# Power.net
KiCad netlist of a schematic drawn in Altium Designer
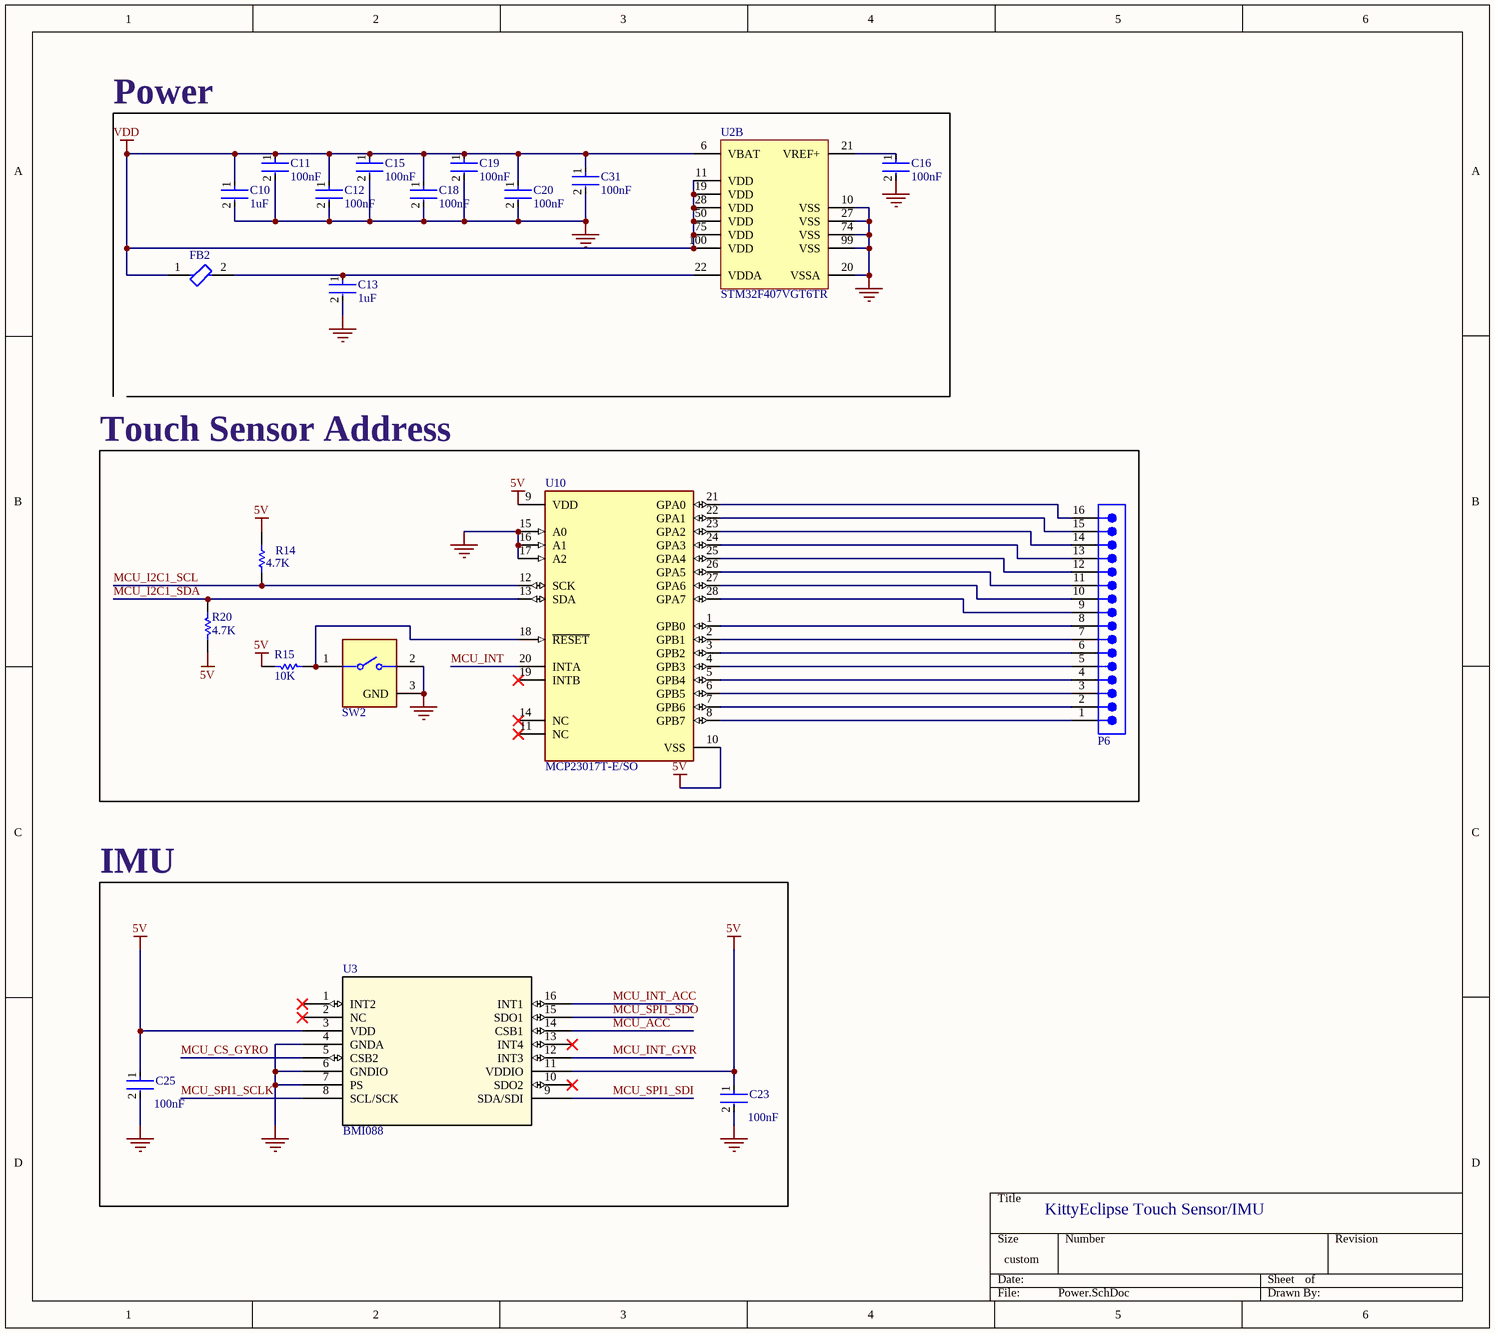
[diagram p0: Power.SchDoc]

(export (version "E")
  (design (tool "Eeschema 10.0.6"))
  (components
    (comp (ref "C10")
      (value "1uF")
      (footprint "FP-CL10-IPC_C")
      (description "Cap Ceramic 1uF 10V X7R ±10% Pad SMD 0603 +125°C T/R")
      (fields (field (name "TOLERANCE") "10%"))
      (libsource (lib "Altium Content Vault") (part "b4654b650e69147ec39a6b967a45e02"))
    )
    (comp (ref "C11")
      (value "100nF")
      (footprint "FP-CL93-IPC_C")
      (description "Cap Ceramic 100nF 10V X7R ±10% SMD 0402 +125°C Paper T/R")
      (libsource (lib "Altium Content Vault") (part "b4654b650e69147ec39a6b967a45e02"))
    )
    (comp (ref "C12")
      (value "100nF")
      (footprint "FP-CL93-IPC_C")
      (description "Cap Ceramic 100nF 10V X7R ±10% SMD 0402 +125°C Paper T/R")
      (libsource (lib "Altium Content Vault") (part "b4654b650e69147ec39a6b967a45e02"))
    )
    (comp (ref "C13")
      (value "1uF")
      (footprint "FP-CL10-IPC_C")
      (description "Cap Ceramic 1uF 10V X7R ±10% Pad SMD 0603 +125°C T/R")
      (fields (field (name "TOLERANCE") "10%"))
      (libsource (lib "Altium Content Vault") (part "b4654b650e69147ec39a6b967a45e02"))
    )
    (comp (ref "C15")
      (value "100nF")
      (footprint "FP-CL93-IPC_C")
      (description "Cap Ceramic 100nF 10V X7R ±10% SMD 0402 +125°C Paper T/R")
      (libsource (lib "Altium Content Vault") (part "b4654b650e69147ec39a6b967a45e02"))
    )
    (comp (ref "C16")
      (value "100nF")
      (footprint "FP-CL93-IPC_C")
      (description "Cap Ceramic 100nF 10V X7R ±10% SMD 0402 +125°C Paper T/R")
      (libsource (lib "Altium Content Vault") (part "b4654b650e69147ec39a6b967a45e02"))
    )
    (comp (ref "C18")
      (value "100nF")
      (footprint "FP-CL93-IPC_C")
      (description "Cap Ceramic 100nF 10V X7R ±10% SMD 0402 +125°C Paper T/R")
      (libsource (lib "Altium Content Vault") (part "b4654b650e69147ec39a6b967a45e02"))
    )
    (comp (ref "C19")
      (value "100nF")
      (footprint "FP-CL93-IPC_C")
      (description "Cap Ceramic 100nF 10V X7R ±10% SMD 0402 +125°C Paper T/R")
      (libsource (lib "Altium Content Vault") (part "b4654b650e69147ec39a6b967a45e02"))
    )
    (comp (ref "C20")
      (value "100nF")
      (footprint "FP-CL93-IPC_C")
      (description "Cap Ceramic 100nF 10V X7R ±10% SMD 0402 +125°C Paper T/R")
      (libsource (lib "Altium Content Vault") (part "b4654b650e69147ec39a6b967a45e02"))
    )
    (comp (ref "C23")
      (value "100nF")
      (footprint "FP-CL93-IPC_C")
      (description "Cap Ceramic 100nF 10V X7R ±10% SMD 0402 +125°C Paper T/R")
      (libsource (lib "Altium Content Vault") (part "b4654b650e69147ec39a6b967a45e02"))
    )
    (comp (ref "C25")
      (value "100nF")
      (footprint "FP-CL93-IPC_C")
      (description "Cap Ceramic 100nF 10V X7R ±10% SMD 0402 +125°C Paper T/R")
      (libsource (lib "Altium Content Vault") (part "b4654b650e69147ec39a6b967a45e02"))
    )
    (comp (ref "C31")
      (value "100nF")
      (footprint "FP-CL93-IPC_C")
      (description "Cap Ceramic 100nF 10V X7R ±10% SMD 0402 +125°C Paper T/R")
      (libsource (lib "Altium Content Vault") (part "b4654b650e69147ec39a6b967a45e02"))
    )
    (comp (ref "FB2")
      (value "600ohm")
      (footprint "FP-BLM15-0_05-MFG")
      (description "Chip Ferrite Bead, 0402, 600Ω @ 100MHz, 0.52Ω, 25%, 300mA")
      (fields (field (name "TOLERANCE") "25%"))
      (libsource (lib "Altium Content Vault") (part "5f30dd21d616792df468990f7003faa"))
    )
    (comp (ref "P6")
      (value "61301611121")
      (footprint "61301611121")
      (libsource (lib "Altium Content Vault") (part "Header_Male_1R_16P"))
    )
    (comp (ref "R14")
      (value "4.7K")
      (footprint "RESC1608X55X25LL10T15")
      (description "Chip Resistor, 4.7 KOhm, +/- 1%, 0.1 W, -55 to 155 degC, 0603 (1608 Metric), RoHS, Tape and Reel")
      (fields (field (name "MANUFACTURER") "Yageo") (field (name "TOLERANCE") "1%"))
      (libsource (lib "Altium Content Vault") (part "RES-2"))
    )
    (comp (ref "R15")
      (value "10K")
      (footprint "RESC1608X55X25ML10T15")
      (description "Resistor, 10 KOhm, +/- 5%, 100 mW, -55 to 155 degC, 0603 (1608 Metric), RoHS, Tape and Reel")
      (fields (field (name "MANUFACTURER") "Yageo") (field (name "TOLERANCE") "5%"))
      (libsource (lib "Altium Content Vault") (part "RES-2"))
    )
    (comp (ref "R20")
      (value "4.7K")
      (footprint "RESC1608X55X25LL10T15")
      (description "Chip Resistor, 4.7 KOhm, +/- 1%, 0.1 W, -55 to 155 degC, 0603 (1608 Metric), RoHS, Tape and Reel")
      (fields (field (name "MANUFACTURER") "Yageo") (field (name "TOLERANCE") "1%"))
      (libsource (lib "Altium Content Vault") (part "RES-2"))
    )
    (comp (ref "SW2")
      (value "B3U-1100PM")
      (footprint "FP-B3U-1100PM-MFG")
      (description "SWITCH TACTILE SPST-NO 0.05A 12V")
      (libsource (lib "Altium Content Vault") (part "6d7322ea62e06c21cb959ab9578dfa0"))
    )
    (comp (ref "U2")
      (value "STM32F407VGT6TR")
      (footprint "STM-LQFP100_L")
      (fields (field (name "MANUFACTURER") "STMicroelectronics"))
      (libsource (lib "Altium Content Vault") (part "MC-ARM-STM32F40X_41X-SQ100"))
    )
    (comp (ref "U3")
      (value "BMI088")
      (footprint "QFN_BMI085_BOS")
      (description "No Description Available")
      (libsource (lib "BMI088") (part "BMI088"))
    )
    (comp (ref "U10")
      (value "MCP23017T-E/SO")
      (footprint "FP-C04-052-MFG")
      (description "IC I/O EXPANDER I2C 16B 28SOIC")
      (libsource (lib "Altium Content Vault") (part "5a9070f3ac31e52c3c9f34e69183557"))
    )
  )
  (nets
    (net (code "1") (name "/MCU_ACC") (class "Default")
      (node (ref "U3") (pin "14") (pinfunction "CSB1_14") (pintype "bidirectional"))
    )
    (net (code "2") (name "/MCU_CS_GYRO") (class "Default")
      (node (ref "U3") (pin "5") (pinfunction "CSB2_5") (pintype "bidirectional"))
    )
    (net (code "3") (name "/MCU_I2C1_SCL") (class "Default")
      (node (ref "R14") (pin "2") (pinfunction "2_2") (pintype "passive"))
      (node (ref "U10") (pin "12") (pinfunction "SCK_12") (pintype "bidirectional"))
    )
    (net (code "4") (name "/MCU_I2C1_SDA") (class "Default")
      (node (ref "R20") (pin "2") (pinfunction "2_2") (pintype "passive"))
      (node (ref "U10") (pin "13") (pinfunction "SDA_13") (pintype "bidirectional"))
    )
    (net (code "5") (name "/MCU_INT") (class "Default")
      (node (ref "U10") (pin "20") (pinfunction "INTA_20") (pintype "open_collector"))
    )
    (net (code "6") (name "/MCU_INT_ACC") (class "Default")
      (node (ref "U3") (pin "16") (pinfunction "INT1_16") (pintype "bidirectional"))
    )
    (net (code "7") (name "/MCU_INT_GYR") (class "Default")
      (node (ref "U3") (pin "12") (pinfunction "INT3_12") (pintype "bidirectional"))
    )
    (net (code "8") (name "/MCU_SPI1_SCLK") (class "Default")
      (node (ref "U3") (pin "8") (pinfunction "SCL/SCK_8") (pintype "passive"))
    )
    (net (code "9") (name "/MCU_SPI1_SDI") (class "Default")
      (node (ref "U3") (pin "9") (pinfunction "SDA/SDI_9") (pintype "passive"))
    )
    (net (code "10") (name "/MCU_SPI1_SDO") (class "Default")
      (node (ref "U3") (pin "15") (pinfunction "SDO1_15") (pintype "bidirectional"))
    )
    (net (code "11") (name "5V") (class "Default")
      (node (ref "C23") (pin "1") (pinfunction "1_1") (pintype "passive"))
      (node (ref "C25") (pin "1") (pinfunction "1_1") (pintype "passive"))
      (node (ref "R14") (pin "1") (pinfunction "1_1") (pintype "passive"))
      (node (ref "R15") (pin "1") (pinfunction "1_1") (pintype "passive"))
      (node (ref "R20") (pin "1") (pinfunction "1_1") (pintype "passive"))
      (node (ref "U10") (pin "10") (pinfunction "VSS_10") (pintype "power_in"))
      (node (ref "U10") (pin "9") (pinfunction "VDD_9") (pintype "power_in"))
      (node (ref "U3") (pin "11") (pinfunction "VDDIO_11") (pintype "power_in"))
      (node (ref "U3") (pin "3") (pinfunction "VDD_3") (pintype "power_in"))
    )
    (net (code "12") (name "GND") (class "Default")
      (node (ref "C10") (pin "2") (pinfunction "2_2") (pintype "passive"))
      (node (ref "C11") (pin "2") (pinfunction "2_2") (pintype "passive"))
      (node (ref "C12") (pin "2") (pinfunction "2_2") (pintype "passive"))
      (node (ref "C13") (pin "2") (pinfunction "2_2") (pintype "passive"))
      (node (ref "C15") (pin "2") (pinfunction "2_2") (pintype "passive"))
      (node (ref "C16") (pin "2") (pinfunction "2_2") (pintype "passive"))
      (node (ref "C18") (pin "2") (pinfunction "2_2") (pintype "passive"))
      (node (ref "C19") (pin "2") (pinfunction "2_2") (pintype "passive"))
      (node (ref "C20") (pin "2") (pinfunction "2_2") (pintype "passive"))
      (node (ref "C23") (pin "2") (pinfunction "2_2") (pintype "passive"))
      (node (ref "C25") (pin "2") (pinfunction "2_2") (pintype "passive"))
      (node (ref "C31") (pin "2") (pinfunction "2_2") (pintype "passive"))
      (node (ref "SW2") (pin "2") (pinfunction "2_2") (pintype "passive"))
      (node (ref "SW2") (pin "3") (pinfunction "GND_3") (pintype "power_in"))
      (node (ref "U10") (pin "15") (pinfunction "A0_15") (pintype "input"))
      (node (ref "U10") (pin "16") (pinfunction "A1_16") (pintype "input"))
      (node (ref "U10") (pin "17") (pinfunction "A2_17") (pintype "input"))
      (node (ref "U2") (pin "10") (pinfunction "VSS_10") (pintype "power_in"))
      (node (ref "U2") (pin "20") (pinfunction "VSSA_20") (pintype "power_in"))
      (node (ref "U2") (pin "27") (pinfunction "VSS_27") (pintype "power_in"))
      (node (ref "U2") (pin "74") (pinfunction "VSS_74") (pintype "power_in"))
      (node (ref "U2") (pin "99") (pinfunction "VSS_99") (pintype "power_in"))
      (node (ref "U3") (pin "4") (pinfunction "GNDA_4") (pintype "power_in"))
      (node (ref "U3") (pin "6") (pinfunction "GNDIO_6") (pintype "power_in"))
      (node (ref "U3") (pin "7") (pinfunction "PS_7") (pintype "passive"))
    )
    (net (code "13") (name "Net-(U2B-VDDA)") (class "Default")
      (node (ref "C13") (pin "1") (pinfunction "1_1") (pintype "passive"))
      (node (ref "FB2") (pin "2") (pinfunction "2_2") (pintype "passive"))
      (node (ref "U2") (pin "22") (pinfunction "VDDA_22") (pintype "power_in"))
    )
    (net (code "14") (name "Net-(U2B-VREF+)") (class "Default")
      (node (ref "C16") (pin "1") (pinfunction "1_1") (pintype "passive"))
      (node (ref "U2") (pin "21") (pinfunction "VREF+_21") (pintype "power_in"))
    )
    (net (code "15") (name "Net-(U10-GPA0)") (class "Default")
      (node (ref "P6") (pin "16") (pinfunction "16_16") (pintype "passive"))
      (node (ref "U10") (pin "21") (pinfunction "GPA0_21") (pintype "bidirectional"))
    )
    (net (code "16") (name "Net-(U10-GPA1)") (class "Default")
      (node (ref "P6") (pin "15") (pinfunction "15_15") (pintype "passive"))
      (node (ref "U10") (pin "22") (pinfunction "GPA1_22") (pintype "bidirectional"))
    )
    (net (code "17") (name "Net-(U10-GPA2)") (class "Default")
      (node (ref "P6") (pin "14") (pinfunction "14_14") (pintype "passive"))
      (node (ref "U10") (pin "23") (pinfunction "GPA2_23") (pintype "bidirectional"))
    )
    (net (code "18") (name "Net-(U10-GPA3)") (class "Default")
      (node (ref "P6") (pin "13") (pinfunction "13_13") (pintype "passive"))
      (node (ref "U10") (pin "24") (pinfunction "GPA3_24") (pintype "bidirectional"))
    )
    (net (code "19") (name "Net-(U10-GPA4)") (class "Default")
      (node (ref "P6") (pin "12") (pinfunction "12_12") (pintype "passive"))
      (node (ref "U10") (pin "25") (pinfunction "GPA4_25") (pintype "bidirectional"))
    )
    (net (code "20") (name "Net-(U10-GPA5)") (class "Default")
      (node (ref "P6") (pin "11") (pinfunction "11_11") (pintype "passive"))
      (node (ref "U10") (pin "26") (pinfunction "GPA5_26") (pintype "bidirectional"))
    )
    (net (code "21") (name "Net-(U10-GPA6)") (class "Default")
      (node (ref "P6") (pin "10") (pinfunction "10_10") (pintype "passive"))
      (node (ref "U10") (pin "27") (pinfunction "GPA6_27") (pintype "bidirectional"))
    )
    (net (code "22") (name "Net-(U10-GPA7)") (class "Default")
      (node (ref "P6") (pin "9") (pinfunction "9_9") (pintype "passive"))
      (node (ref "U10") (pin "28") (pinfunction "GPA7_28") (pintype "bidirectional"))
    )
    (net (code "23") (name "Net-(U10-GPB0)") (class "Default")
      (node (ref "P6") (pin "8") (pinfunction "8_8") (pintype "passive"))
      (node (ref "U10") (pin "1") (pinfunction "GPB0_1") (pintype "bidirectional"))
    )
    (net (code "24") (name "Net-(U10-GPB1)") (class "Default")
      (node (ref "P6") (pin "7") (pinfunction "7_7") (pintype "passive"))
      (node (ref "U10") (pin "2") (pinfunction "GPB1_2") (pintype "bidirectional"))
    )
    (net (code "25") (name "Net-(U10-GPB2)") (class "Default")
      (node (ref "P6") (pin "6") (pinfunction "6_6") (pintype "passive"))
      (node (ref "U10") (pin "3") (pinfunction "GPB2_3") (pintype "bidirectional"))
    )
    (net (code "26") (name "Net-(U10-GPB3)") (class "Default")
      (node (ref "P6") (pin "5") (pinfunction "5_5") (pintype "passive"))
      (node (ref "U10") (pin "4") (pinfunction "GPB3_4") (pintype "bidirectional"))
    )
    (net (code "27") (name "Net-(U10-GPB4)") (class "Default")
      (node (ref "P6") (pin "4") (pinfunction "4_4") (pintype "passive"))
      (node (ref "U10") (pin "5") (pinfunction "GPB4_5") (pintype "bidirectional"))
    )
    (net (code "28") (name "Net-(U10-GPB5)") (class "Default")
      (node (ref "P6") (pin "3") (pinfunction "3_3") (pintype "passive"))
      (node (ref "U10") (pin "6") (pinfunction "GPB5_6") (pintype "bidirectional"))
    )
    (net (code "29") (name "Net-(U10-GPB6)") (class "Default")
      (node (ref "P6") (pin "2") (pinfunction "2_2") (pintype "passive"))
      (node (ref "U10") (pin "7") (pinfunction "GPB6_7") (pintype "bidirectional"))
    )
    (net (code "30") (name "Net-(U10-GPB7)") (class "Default")
      (node (ref "P6") (pin "1") (pinfunction "1_1") (pintype "passive"))
      (node (ref "U10") (pin "8") (pinfunction "GPB7_8") (pintype "bidirectional"))
    )
    (net (code "31") (name "Net-(U10-~{RESET})") (class "Default")
      (node (ref "R15") (pin "2") (pinfunction "2_2") (pintype "passive"))
      (node (ref "SW2") (pin "1") (pinfunction "1_1") (pintype "passive"))
      (node (ref "U10") (pin "18") (pinfunction "~{RESET}_18") (pintype "input"))
    )
    (net (code "32") (name "VDD") (class "Default")
      (node (ref "C10") (pin "1") (pinfunction "1_1") (pintype "passive"))
      (node (ref "C11") (pin "1") (pinfunction "1_1") (pintype "passive"))
      (node (ref "C12") (pin "1") (pinfunction "1_1") (pintype "passive"))
      (node (ref "C15") (pin "1") (pinfunction "1_1") (pintype "passive"))
      (node (ref "C18") (pin "1") (pinfunction "1_1") (pintype "passive"))
      (node (ref "C19") (pin "1") (pinfunction "1_1") (pintype "passive"))
      (node (ref "C20") (pin "1") (pinfunction "1_1") (pintype "passive"))
      (node (ref "C31") (pin "1") (pinfunction "1_1") (pintype "passive"))
      (node (ref "FB2") (pin "1") (pinfunction "1_1") (pintype "passive"))
      (node (ref "U2") (pin "100") (pinfunction "VDD_100") (pintype "power_in"))
      (node (ref "U2") (pin "11") (pinfunction "VDD_11") (pintype "power_in"))
      (node (ref "U2") (pin "19") (pinfunction "VDD_19") (pintype "power_in"))
      (node (ref "U2") (pin "28") (pinfunction "VDD_28") (pintype "power_in"))
      (node (ref "U2") (pin "50") (pinfunction "VDD_50") (pintype "power_in"))
      (node (ref "U2") (pin "6") (pinfunction "VBAT_6") (pintype "power_in"))
      (node (ref "U2") (pin "75") (pinfunction "VDD_75") (pintype "power_in"))
    )
    (net (code "33") (name "unconnected-(U3-INT2-Pad1)") (class "Default")
      (node (ref "U3") (pin "1") (pinfunction "INT2_1") (pintype "bidirectional+no_connect"))
    )
    (net (code "34") (name "unconnected-(U3-INT4-Pad13)") (class "Default")
      (node (ref "U3") (pin "13") (pinfunction "INT4_13") (pintype "bidirectional+no_connect"))
    )
    (net (code "35") (name "unconnected-(U3-NC-Pad2)") (class "Default")
      (node (ref "U3") (pin "2") (pinfunction "NC_2") (pintype "passive+no_connect"))
    )
    (net (code "36") (name "unconnected-(U3-SDO2-Pad10)") (class "Default")
      (node (ref "U3") (pin "10") (pinfunction "SDO2_10") (pintype "bidirectional+no_connect"))
    )
    (net (code "37") (name "unconnected-(U10-INTB-Pad19)") (class "Default")
      (node (ref "U10") (pin "19") (pinfunction "INTB_19") (pintype "open_collector+no_connect"))
    )
    (net (code "38") (name "unconnected-(U10-NC-Pad11)") (class "Default")
      (node (ref "U10") (pin "11") (pinfunction "NC_11") (pintype "passive+no_connect"))
    )
    (net (code "39") (name "unconnected-(U10-NC-Pad14)") (class "Default")
      (node (ref "U10") (pin "14") (pinfunction "NC_14") (pintype "passive+no_connect"))
    )
  )
)
